# heart_necklace.net
KiCad netlist of a schematic drawn in EAGLE
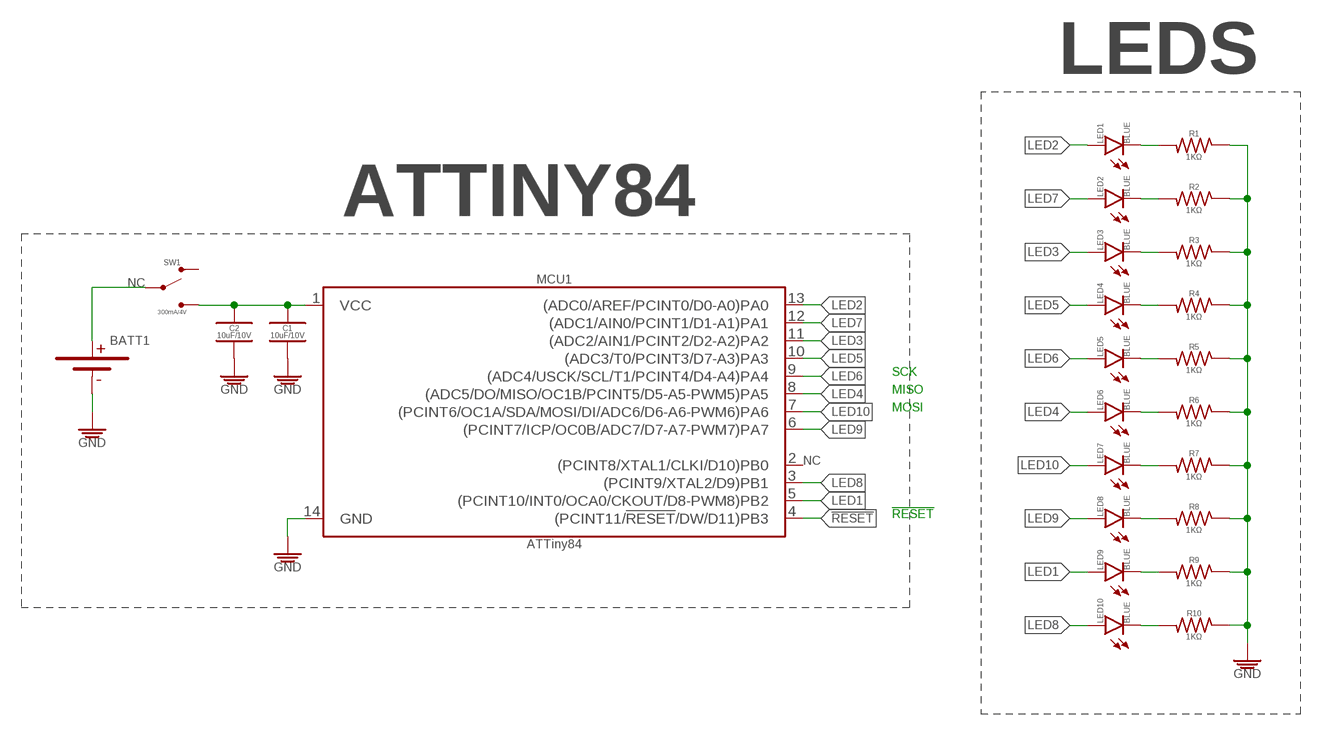
[diagram p0: schematic, sheet 1]

(export (version "E")
  (design (tool "Eeschema 10.0.6"))
  (components
    (comp (ref "BATT1")
      (value "BATTERY_COIN-CELL_SMD_3V_20MM")
      (footprint "eagle-import:CR-2032")
      (libsource (lib "eagle-import") (part "BATTERY_COIN-CELL_SMD_3V_20MM"))
    )
    (comp (ref "C1")
      (value "10uF/10V")
      (footprint "eagle-import:_CER_SMD_0402")
      (fields
        (field (name "MFR") "Samsung Electro-Mechanics")
        (field (name "MPN") "CL05A106MP5NUNC")
        (field (name "CREATOR") "MrSwirlyEyes")
      )
      (libsource (lib "eagle-import") (part "10UF_CER_SMD-0402_10V-20%"))
    )
    (comp (ref "C2")
      (value "10uF/10V")
      (footprint "eagle-import:_CER_SMD_0402")
      (fields
        (field (name "MFR") "Samsung Electro-Mechanics")
        (field (name "MPN") "CL05A106MP5NUNC")
        (field (name "CREATOR") "MrSwirlyEyes")
      )
      (libsource (lib "eagle-import") (part "10UF_CER_SMD-0402_10V-20%"))
    )
    (comp (ref "LED1")
      (value "BLUE")
      (footprint "eagle-import:LED_SMD-805_NO-SILK")
      (libsource (lib "eagle-import") (part "LED_SMD-0805_DISCRETE_NO-COLOR_NO-SILK"))
    )
    (comp (ref "LED2")
      (value "BLUE")
      (footprint "eagle-import:LED_SMD-805_NO-SILK")
      (libsource (lib "eagle-import") (part "LED_SMD-0805_DISCRETE_NO-COLOR_NO-SILK"))
    )
    (comp (ref "LED3")
      (value "BLUE")
      (footprint "eagle-import:LED_SMD-805_NO-SILK")
      (libsource (lib "eagle-import") (part "LED_SMD-0805_DISCRETE_NO-COLOR_NO-SILK"))
    )
    (comp (ref "LED4")
      (value "BLUE")
      (footprint "eagle-import:LED_SMD-805_NO-SILK")
      (libsource (lib "eagle-import") (part "LED_SMD-0805_DISCRETE_NO-COLOR_NO-SILK"))
    )
    (comp (ref "LED5")
      (value "BLUE")
      (footprint "eagle-import:LED_SMD-805_NO-SILK")
      (libsource (lib "eagle-import") (part "LED_SMD-0805_DISCRETE_NO-COLOR_NO-SILK"))
    )
    (comp (ref "LED6")
      (value "BLUE")
      (footprint "eagle-import:LED_SMD-805_NO-SILK")
      (libsource (lib "eagle-import") (part "LED_SMD-0805_DISCRETE_NO-COLOR_NO-SILK"))
    )
    (comp (ref "LED7")
      (value "BLUE")
      (footprint "eagle-import:LED_SMD-805_NO-SILK")
      (libsource (lib "eagle-import") (part "LED_SMD-0805_DISCRETE_NO-COLOR_NO-SILK"))
    )
    (comp (ref "LED8")
      (value "BLUE")
      (footprint "eagle-import:LED_SMD-805_NO-SILK")
      (libsource (lib "eagle-import") (part "LED_SMD-0805_DISCRETE_NO-COLOR_NO-SILK"))
    )
    (comp (ref "LED9")
      (value "BLUE")
      (footprint "eagle-import:LED_SMD-805_NO-SILK")
      (libsource (lib "eagle-import") (part "LED_SMD-0805_DISCRETE_NO-COLOR_NO-SILK"))
    )
    (comp (ref "LED10")
      (value "BLUE")
      (footprint "eagle-import:LED_SMD-805_NO-SILK")
      (libsource (lib "eagle-import") (part "LED_SMD-0805_DISCRETE_NO-COLOR_NO-SILK"))
    )
    (comp (ref "MCU1")
      (value "ATTiny84")
      (footprint "eagle-import:SO-14_NO-SILK")
      (fields (field (name "MFR") "Microchip Technology") (field (name "MPN") "ATTINY84A-SSU"))
      (libsource (lib "eagle-import") (part "ATTINY84_SO-14_NO-SILK"))
    )
    (comp (ref "R1")
      (value "1KΩ")
      (footprint "eagle-import:RESISTOR_SMD-805")
      (fields
        (field (name "MFR") "Yageo")
        (field (name "MPN") "RC0805JR-071KL ")
        (field (name "CREATOR") "Kenmei")
      )
      (libsource (lib "eagle-import") (part "1KΩ_SMD-0805_1/8W-5%"))
    )
    (comp (ref "R2")
      (value "1KΩ")
      (footprint "eagle-import:RESISTOR_SMD-805")
      (fields
        (field (name "MFR") "Yageo")
        (field (name "MPN") "RC0805JR-071KL ")
        (field (name "CREATOR") "Kenmei")
      )
      (libsource (lib "eagle-import") (part "1KΩ_SMD-0805_1/8W-5%"))
    )
    (comp (ref "R3")
      (value "1KΩ")
      (footprint "eagle-import:RESISTOR_SMD-805")
      (fields
        (field (name "MFR") "Yageo")
        (field (name "MPN") "RC0805JR-071KL ")
        (field (name "CREATOR") "Kenmei")
      )
      (libsource (lib "eagle-import") (part "1KΩ_SMD-0805_1/8W-5%"))
    )
    (comp (ref "R4")
      (value "1KΩ")
      (footprint "eagle-import:RESISTOR_SMD-805")
      (fields
        (field (name "MFR") "Yageo")
        (field (name "MPN") "RC0805JR-071KL ")
        (field (name "CREATOR") "Kenmei")
      )
      (libsource (lib "eagle-import") (part "1KΩ_SMD-0805_1/8W-5%"))
    )
    (comp (ref "R5")
      (value "1KΩ")
      (footprint "eagle-import:RESISTOR_SMD-805")
      (fields
        (field (name "MFR") "Yageo")
        (field (name "MPN") "RC0805JR-071KL ")
        (field (name "CREATOR") "Kenmei")
      )
      (libsource (lib "eagle-import") (part "1KΩ_SMD-0805_1/8W-5%"))
    )
    (comp (ref "R6")
      (value "1KΩ")
      (footprint "eagle-import:RESISTOR_SMD-805")
      (fields
        (field (name "MFR") "Yageo")
        (field (name "MPN") "RC0805JR-071KL ")
        (field (name "CREATOR") "Kenmei")
      )
      (libsource (lib "eagle-import") (part "1KΩ_SMD-0805_1/8W-5%"))
    )
    (comp (ref "R7")
      (value "1KΩ")
      (footprint "eagle-import:RESISTOR_SMD-805")
      (fields
        (field (name "MFR") "Yageo")
        (field (name "MPN") "RC0805JR-071KL ")
        (field (name "CREATOR") "Kenmei")
      )
      (libsource (lib "eagle-import") (part "1KΩ_SMD-0805_1/8W-5%"))
    )
    (comp (ref "R8")
      (value "1KΩ")
      (footprint "eagle-import:RESISTOR_SMD-805")
      (fields
        (field (name "MFR") "Yageo")
        (field (name "MPN") "RC0805JR-071KL ")
        (field (name "CREATOR") "Kenmei")
      )
      (libsource (lib "eagle-import") (part "1KΩ_SMD-0805_1/8W-5%"))
    )
    (comp (ref "R9")
      (value "1KΩ")
      (footprint "eagle-import:RESISTOR_SMD-805")
      (fields
        (field (name "MFR") "Yageo")
        (field (name "MPN") "RC0805JR-071KL ")
        (field (name "CREATOR") "Kenmei")
      )
      (libsource (lib "eagle-import") (part "1KΩ_SMD-0805_1/8W-5%"))
    )
    (comp (ref "R10")
      (value "1KΩ")
      (footprint "eagle-import:RESISTOR_SMD-805")
      (fields
        (field (name "MFR") "Yageo")
        (field (name "MPN") "RC0805JR-071KL ")
        (field (name "CREATOR") "Kenmei")
      )
      (libsource (lib "eagle-import") (part "1KΩ_SMD-0805_1/8W-5%"))
    )
    (comp (ref "SW1")
      (value "300mA/4V")
      (footprint "eagle-import:SW_SLIDE_SPDT_RA_SMD_4V_300MA_6.7L-2.6W")
      (fields
        (field (name "MFR") "APEM Inc.")
        (field (name "MPN") "MA12RTR")
        (field (name "CREATOR") "MrSwirlyEyes")
      )
      (libsource (lib "eagle-import") (part "SWITCH_SPDT_RA_SMD_300MA-4V_6.7L-2.6W"))
    )
  )
  (nets
    (net (code "1") (name "/~{RESET}") (class "Default")
      (node (ref "MCU1") (pin "4") (pinfunction "(PCINT11/~{RESET}/DW/D11)PB3_4") (pintype "bidirectional"))
    )
    (net (code "2") (name "GND") (class "Default")
      (node (ref "BATT1") (pin "-") (pinfunction "-_-") (pintype "bidirectional"))
      (node (ref "C1") (pin "2") (pinfunction "2_2") (pintype "passive"))
      (node (ref "C2") (pin "2") (pinfunction "2_2") (pintype "passive"))
      (node (ref "MCU1") (pin "14") (pinfunction "GND_14") (pintype "passive"))
      (node (ref "R1") (pin "1") (pinfunction "1_1") (pintype "passive"))
      (node (ref "R10") (pin "1") (pinfunction "1_1") (pintype "passive"))
      (node (ref "R2") (pin "1") (pinfunction "1_1") (pintype "passive"))
      (node (ref "R3") (pin "1") (pinfunction "1_1") (pintype "passive"))
      (node (ref "R4") (pin "1") (pinfunction "1_1") (pintype "passive"))
      (node (ref "R5") (pin "1") (pinfunction "1_1") (pintype "passive"))
      (node (ref "R6") (pin "1") (pinfunction "1_1") (pintype "passive"))
      (node (ref "R7") (pin "1") (pinfunction "1_1") (pintype "passive"))
      (node (ref "R8") (pin "1") (pinfunction "1_1") (pintype "passive"))
      (node (ref "R9") (pin "1") (pinfunction "1_1") (pintype "passive"))
    )
    (net (code "3") (name "LED1") (class "Default")
      (node (ref "LED9") (pin "A") (pinfunction "A_A") (pintype "passive"))
      (node (ref "MCU1") (pin "5") (pinfunction "(PCINT10/INT0/OCA0/CKOUT/D8-PWM8)PB2_5") (pintype "bidirectional"))
    )
    (net (code "4") (name "LED2") (class "Default")
      (node (ref "LED1") (pin "A") (pinfunction "A_A") (pintype "passive"))
      (node (ref "MCU1") (pin "13") (pinfunction "(ADC0/AREF/PCINT0/D0-A0)PA0_13") (pintype "bidirectional"))
    )
    (net (code "5") (name "LED3") (class "Default")
      (node (ref "LED3") (pin "A") (pinfunction "A_A") (pintype "passive"))
      (node (ref "MCU1") (pin "11") (pinfunction "(ADC2/AIN1/PCINT2/D2-A2)PA2_11") (pintype "bidirectional"))
    )
    (net (code "6") (name "LED4") (class "Default")
      (node (ref "LED6") (pin "A") (pinfunction "A_A") (pintype "passive"))
      (node (ref "MCU1") (pin "8") (pinfunction "(ADC5/DO/MISO/OC1B/PCINT5/D5-A5-PWM5)PA5_8") (pintype "bidirectional"))
    )
    (net (code "7") (name "LED5") (class "Default")
      (node (ref "LED4") (pin "A") (pinfunction "A_A") (pintype "passive"))
      (node (ref "MCU1") (pin "10") (pinfunction "(ADC3/T0/PCINT3/D7-A3)PA3_10") (pintype "bidirectional"))
    )
    (net (code "8") (name "LED6") (class "Default")
      (node (ref "LED5") (pin "A") (pinfunction "A_A") (pintype "passive"))
      (node (ref "MCU1") (pin "9") (pinfunction "(ADC4/USCK/SCL/T1/PCINT4/D4-A4)PA4_9") (pintype "bidirectional"))
    )
    (net (code "9") (name "LED7") (class "Default")
      (node (ref "LED2") (pin "A") (pinfunction "A_A") (pintype "passive"))
      (node (ref "MCU1") (pin "12") (pinfunction "(ADC1/AIN0/PCINT1/D1-A1)PA1_12") (pintype "bidirectional"))
    )
    (net (code "10") (name "LED8") (class "Default")
      (node (ref "LED10") (pin "A") (pinfunction "A_A") (pintype "passive"))
      (node (ref "MCU1") (pin "3") (pinfunction "(PCINT9/XTAL2/D9)PB1_3") (pintype "bidirectional"))
    )
    (net (code "11") (name "LED9") (class "Default")
      (node (ref "LED8") (pin "A") (pinfunction "A_A") (pintype "passive"))
      (node (ref "MCU1") (pin "6") (pinfunction "(PCINT7/ICP/OC0B/ADC7/D7-A7-PWM7)PA7_6") (pintype "bidirectional"))
    )
    (net (code "12") (name "LED10") (class "Default")
      (node (ref "LED7") (pin "A") (pinfunction "A_A") (pintype "passive"))
      (node (ref "MCU1") (pin "7") (pinfunction "(PCINT6/OC1A/SDA/MOSI/DI/ADC6/D6-A6-PWM6)PA6_7") (pintype "bidirectional"))
    )
    (net (code "13") (name "Net-(BATT1-+-Pad+_1)") (class "Default")
      (node (ref "BATT1") (pin "+_1") (pinfunction "+_+_1") (pintype "bidirectional"))
      (node (ref "BATT1") (pin "+_2") (pinfunction "+_+_2") (pintype "bidirectional"))
      (node (ref "SW1") (pin "2") (pinfunction "2_2") (pintype "passive"))
    )
    (net (code "14") (name "Net-(LED1-PadK)") (class "Default")
      (node (ref "LED1") (pin "K") (pinfunction "K_K") (pintype "passive"))
      (node (ref "R1") (pin "2") (pinfunction "2_2") (pintype "passive"))
    )
    (net (code "15") (name "Net-(LED2-PadK)") (class "Default")
      (node (ref "LED2") (pin "K") (pinfunction "K_K") (pintype "passive"))
      (node (ref "R2") (pin "2") (pinfunction "2_2") (pintype "passive"))
    )
    (net (code "16") (name "Net-(LED3-PadK)") (class "Default")
      (node (ref "LED3") (pin "K") (pinfunction "K_K") (pintype "passive"))
      (node (ref "R3") (pin "2") (pinfunction "2_2") (pintype "passive"))
    )
    (net (code "17") (name "Net-(LED4-PadK)") (class "Default")
      (node (ref "LED4") (pin "K") (pinfunction "K_K") (pintype "passive"))
      (node (ref "R4") (pin "2") (pinfunction "2_2") (pintype "passive"))
    )
    (net (code "18") (name "Net-(LED5-PadK)") (class "Default")
      (node (ref "LED5") (pin "K") (pinfunction "K_K") (pintype "passive"))
      (node (ref "R5") (pin "2") (pinfunction "2_2") (pintype "passive"))
    )
    (net (code "19") (name "Net-(LED6-PadK)") (class "Default")
      (node (ref "LED6") (pin "K") (pinfunction "K_K") (pintype "passive"))
      (node (ref "R6") (pin "2") (pinfunction "2_2") (pintype "passive"))
    )
    (net (code "20") (name "Net-(LED7-PadK)") (class "Default")
      (node (ref "LED7") (pin "K") (pinfunction "K_K") (pintype "passive"))
      (node (ref "R7") (pin "2") (pinfunction "2_2") (pintype "passive"))
    )
    (net (code "21") (name "Net-(LED8-PadK)") (class "Default")
      (node (ref "LED8") (pin "K") (pinfunction "K_K") (pintype "passive"))
      (node (ref "R8") (pin "2") (pinfunction "2_2") (pintype "passive"))
    )
    (net (code "22") (name "Net-(LED9-PadK)") (class "Default")
      (node (ref "LED9") (pin "K") (pinfunction "K_K") (pintype "passive"))
      (node (ref "R9") (pin "2") (pinfunction "2_2") (pintype "passive"))
    )
    (net (code "23") (name "Net-(LED10-PadK)") (class "Default")
      (node (ref "LED10") (pin "K") (pinfunction "K_K") (pintype "passive"))
      (node (ref "R10") (pin "2") (pinfunction "2_2") (pintype "passive"))
    )
    (net (code "24") (name "Net-(MCU1-VCC)") (class "Default")
      (node (ref "C1") (pin "1") (pinfunction "1_1") (pintype "passive"))
      (node (ref "C2") (pin "1") (pinfunction "1_1") (pintype "passive"))
      (node (ref "MCU1") (pin "1") (pinfunction "VCC_1") (pintype "passive"))
      (node (ref "SW1") (pin "3") (pinfunction "3_3") (pintype "passive"))
    )
    (net (code "25") (name "unconnected-(MCU1-(PCINT8{slash}XTAL1{slash}CLKI{slash}D10)PB0-Pad2)") (class "Default")
      (node (ref "MCU1") (pin "2") (pinfunction "(PCINT8/XTAL1/CLKI/D10)PB0_2") (pintype "bidirectional"))
    )
    (net (code "26") (name "unconnected-(SW1-Pad1)") (class "Default")
      (node (ref "SW1") (pin "1") (pinfunction "1_1") (pintype "passive"))
    )
  )
)
